# MercurialSDR_FTDI.net
KiCad netlist of a schematic drawn in Altium Designer
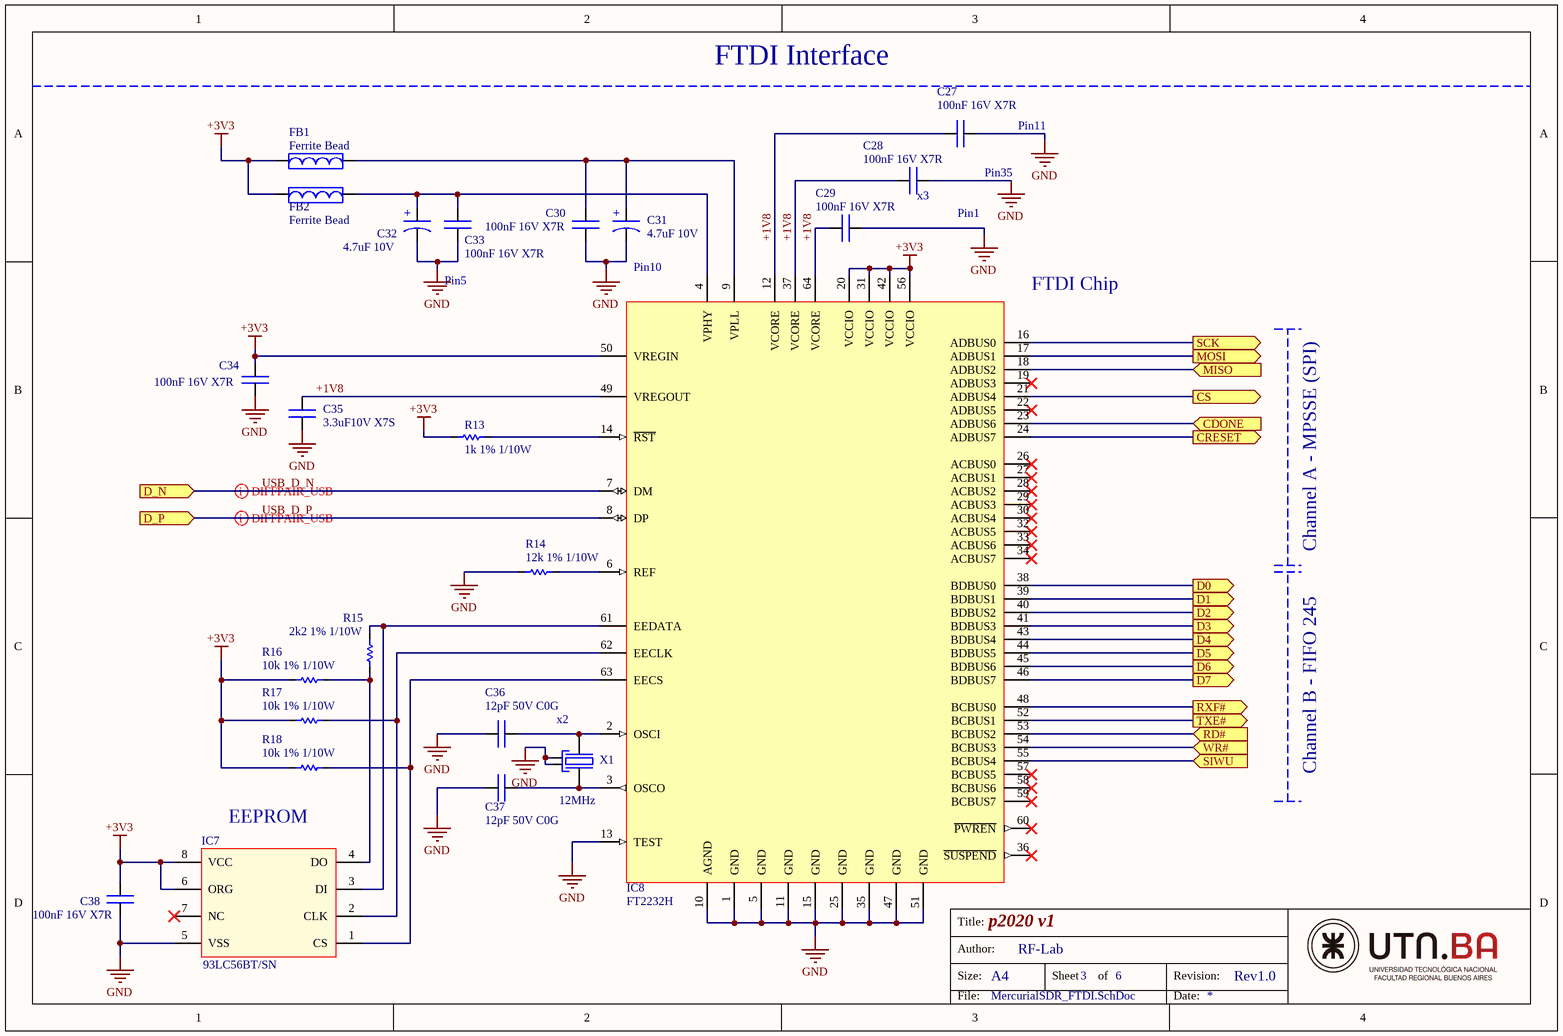
[diagram p0: MercurialSDR_FTDI.SchDoc]

(export (version "E")
  (design (tool "Eeschema 10.0.6"))
  (components
    (comp (ref "C27")
      (value "100nF 16V X7R")
      (footprint "CAP_0603")
      (description "Capacitor no polarizado")
      (fields (field (name "Comment") "100nF 16V X7R - CL10B104KO8NNNC"))
      (libsource (lib "MercurialSDR") (part "Cap"))
    )
    (comp (ref "C28")
      (value "100nF 16V X7R")
      (footprint "CAP_0603")
      (description "Capacitor no polarizado")
      (fields (field (name "Comment") "100nF 16V X7R - CL10B104KO8NNNC"))
      (libsource (lib "MercurialSDR") (part "Cap"))
    )
    (comp (ref "C29")
      (value "100nF 16V X7R")
      (footprint "CAP_0603")
      (description "Capacitor no polarizado")
      (fields (field (name "Comment") "100nF 16V X7R - CL10B104KO8NNNC"))
      (libsource (lib "MercurialSDR") (part "Cap"))
    )
    (comp (ref "C30")
      (value "100nF 16V X7R")
      (footprint "CAP_0603")
      (description "Capacitor no polarizado")
      (fields (field (name "Comment") "100nF 16V X7R - CL10B104KO8NNNC"))
      (libsource (lib "MercurialSDR") (part "Cap"))
    )
    (comp (ref "C31")
      (value "4.7uF 10V")
      (footprint "CAP_TANT_1206")
      (description "Capacitor polarizado")
      (fields (field (name "Comment") "4.7uF 10V - TAJA475K010RNJ"))
      (libsource (lib "MercurialSDR") (part "Cap Pol"))
    )
    (comp (ref "C32")
      (value "4.7uF 10V")
      (footprint "CAP_TANT_1206")
      (description "Capacitor polarizado")
      (fields (field (name "Comment") "4.7uF 10V - TAJA475K010RNJ"))
      (libsource (lib "MercurialSDR") (part "Cap Pol"))
    )
    (comp (ref "C33")
      (value "100nF 16V X7R")
      (footprint "CAP_0603")
      (description "Capacitor no polarizado")
      (fields (field (name "Comment") "100nF 16V X7R - CL10B104KO8NNNC"))
      (libsource (lib "MercurialSDR") (part "Cap"))
    )
    (comp (ref "C34")
      (value "100nF 16V X7R")
      (footprint "CAP_0603")
      (description "Capacitor no polarizado")
      (fields (field (name "Comment") "100nF 16V X7R - CL10B104KO8NNNC"))
      (libsource (lib "MercurialSDR") (part "Cap"))
    )
    (comp (ref "C35")
      (value "3.3uF10V X7S")
      (footprint "CAP_0603")
      (description "Capacitor no polarizado")
      (fields (field (name "Comment") "3.3uF10V X7S - C1608X7S1A335K080AC"))
      (libsource (lib "MercurialSDR") (part "Cap"))
    )
    (comp (ref "C36")
      (value "12pF 50V C0G")
      (footprint "CAP_0603")
      (description "Capacitor no polarizado")
      (fields (field (name "Comment") "12pF 50V C0G - CL10C120JB8NNNC"))
      (libsource (lib "MercurialSDR") (part "Cap"))
    )
    (comp (ref "C37")
      (value "12pF 50V C0G")
      (footprint "CAP_0603")
      (description "Capacitor no polarizado")
      (fields (field (name "Comment") "12pF 50V C0G - CL10C120JB8NNNC"))
      (libsource (lib "MercurialSDR") (part "Cap"))
    )
    (comp (ref "C38")
      (value "100nF 16V X7R")
      (footprint "CAP_0603")
      (description "Capacitor no polarizado")
      (fields
        (field (name "PART NUMBER") "CL10B104KO8NNNC")
        (field (name "Comment") "100nF 16V X7R - CL10B104KO8NNNC")
      )
      (libsource (lib "MercurialSDR") (part "Cap"))
    )
    (comp (ref "FB1")
      (value "BLM18AG121SN1D")
      (footprint "FERRITE_BEAD_0603")
      (description "Ferrite Bead")
      (fields (field (name "IN") "Ferrite Bead"))
      (libsource (lib "MercurialSDR") (part "Ferrite Bead"))
    )
    (comp (ref "FB2")
      (value "BLM18AG121SN1D")
      (footprint "FERRITE_BEAD_0603")
      (description "Ferrite Bead")
      (fields (field (name "IN") "Ferrite Bead"))
      (libsource (lib "MercurialSDR") (part "Ferrite Bead"))
    )
    (comp (ref "IC7")
      (value "93LC56BT")
      (footprint "SOIC-8")
      (description "EEPROM SPI 2kb (128x16)")
      (fields (field (name "PART NUMBER") "93LC56BT/SN"))
      (libsource (lib "MercurialSDR") (part "93LC56BT/SN"))
    )
    (comp (ref "IC8")
      (value "FT2232H")
      (footprint "LQFP_64")
      (description "USB bridge")
      (fields (field (name "Comment") "FT2232HL-TRAY"))
      (libsource (lib "MercurialSDR") (part "FT2232H"))
    )
    (comp (ref "R13")
      (value "1k 1% 1/10W")
      (footprint "RES_0603")
      (description "Resistor")
      (fields (field (name "Comment") "1k 1% 1/10W - CR0603-FX-1001ELF"))
      (libsource (lib "MercurialSDR") (part "Res"))
    )
    (comp (ref "R14")
      (value "12k 1% 1/10W")
      (footprint "RES_0603")
      (description "Resistor")
      (fields (field (name "POWER") "1/10W") (field (name "PART NUMBER") "CR0603-FX-1202ELF"))
      (libsource (lib "MercurialSDR") (part "Res"))
    )
    (comp (ref "R15")
      (value "2k2 1% 1/10W")
      (footprint "RES_0603")
      (description "Resistor")
      (fields (field (name "Comment") "2k2 1% 1/10W - AC0603FR-072K2L"))
      (libsource (lib "MercurialSDR") (part "Res"))
    )
    (comp (ref "R16")
      (value "10k 1% 1/10W")
      (footprint "RES_0603")
      (description "Resistor")
      (fields (field (name "Comment") "10k 1% 1/10W - CR0603-FX-1002EAS"))
      (libsource (lib "MercurialSDR") (part "Res"))
    )
    (comp (ref "R17")
      (value "10k 1% 1/10W")
      (footprint "RES_0603")
      (description "Resistor")
      (fields (field (name "Comment") "10k 1% 1/10W - CR0603-FX-1002EAS"))
      (libsource (lib "MercurialSDR") (part "Res"))
    )
    (comp (ref "R18")
      (value "10k 1% 1/10W")
      (footprint "RES_0603")
      (description "Resistor")
      (fields (field (name "Comment") "10k 1% 1/10W - CR0603-FX-1002EAS"))
      (libsource (lib "MercurialSDR") (part "Res"))
    )
    (comp (ref "X1")
      (value "12MHz")
      (footprint "XTAL_3.2x2.5")
      (description "Oscilador a Cristal")
      (fields (field (name "PART NUMBER") "ECS-120-12-33-AGN-TR"))
      (libsource (lib "MercurialSDR") (part "XTAL_4term"))
    )
  )
  (nets
    (net (code "1") (name "+3V3") (class "Default")
      (node (ref "C34") (pin "1") (pinfunction "1_1") (pintype "passive"))
      (node (ref "C38") (pin "1") (pinfunction "1_1") (pintype "passive"))
      (node (ref "FB1") (pin "1") (pinfunction "1_1") (pintype "passive"))
      (node (ref "FB2") (pin "1") (pinfunction "1_1") (pintype "passive"))
      (node (ref "IC7") (pin "6") (pinfunction "ORG_6") (pintype "passive"))
      (node (ref "IC7") (pin "8") (pinfunction "VCC_8") (pintype "passive"))
      (node (ref "IC8") (pin "20") (pinfunction "VCCIO_20") (pintype "power_in"))
      (node (ref "IC8") (pin "31") (pinfunction "VCCIO_31") (pintype "power_in"))
      (node (ref "IC8") (pin "42") (pinfunction "VCCIO_42") (pintype "power_in"))
      (node (ref "IC8") (pin "50") (pinfunction "VREGIN_50") (pintype "power_in"))
      (node (ref "IC8") (pin "56") (pinfunction "VCCIO_56") (pintype "power_in"))
      (node (ref "R13") (pin "2") (pinfunction "2_2") (pintype "passive"))
      (node (ref "R16") (pin "2") (pinfunction "2_2") (pintype "passive"))
      (node (ref "R17") (pin "1") (pinfunction "1_1") (pintype "passive"))
      (node (ref "R18") (pin "1") (pinfunction "1_1") (pintype "passive"))
    )
    (net (code "2") (name "/+1V8") (class "Default")
      (node (ref "C27") (pin "1") (pinfunction "1_1") (pintype "passive"))
      (node (ref "C28") (pin "1") (pinfunction "1_1") (pintype "passive"))
      (node (ref "C29") (pin "1") (pinfunction "1_1") (pintype "passive"))
      (node (ref "C35") (pin "1") (pinfunction "1_1") (pintype "passive"))
      (node (ref "IC8") (pin "12") (pinfunction "VCORE_12") (pintype "power_in"))
      (node (ref "IC8") (pin "37") (pinfunction "VCORE_37") (pintype "power_in"))
      (node (ref "IC8") (pin "49") (pinfunction "VREGOUT_49") (pintype "power_in"))
      (node (ref "IC8") (pin "64") (pinfunction "VCORE_64") (pintype "power_in"))
    )
    (net (code "3") (name "/CDONE") (class "Default")
      (node (ref "IC8") (pin "23") (pinfunction "ADBUS6_23") (pintype "passive"))
    )
    (net (code "4") (name "/CRESET") (class "Default")
      (node (ref "IC8") (pin "24") (pinfunction "ADBUS7_24") (pintype "passive"))
    )
    (net (code "5") (name "/CS") (class "Default")
      (node (ref "IC8") (pin "21") (pinfunction "ADBUS4_21") (pintype "passive"))
    )
    (net (code "6") (name "/D0") (class "Default")
      (node (ref "IC8") (pin "38") (pinfunction "BDBUS0_38") (pintype "passive"))
    )
    (net (code "7") (name "/D1") (class "Default")
      (node (ref "IC8") (pin "39") (pinfunction "BDBUS1_39") (pintype "passive"))
    )
    (net (code "8") (name "/D2") (class "Default")
      (node (ref "IC8") (pin "40") (pinfunction "BDBUS2_40") (pintype "passive"))
    )
    (net (code "9") (name "/D3") (class "Default")
      (node (ref "IC8") (pin "41") (pinfunction "BDBUS3_41") (pintype "passive"))
    )
    (net (code "10") (name "/D4") (class "Default")
      (node (ref "IC8") (pin "43") (pinfunction "BDBUS4_43") (pintype "passive"))
    )
    (net (code "11") (name "/D5") (class "Default")
      (node (ref "IC8") (pin "44") (pinfunction "BDBUS5_44") (pintype "passive"))
    )
    (net (code "12") (name "/D6") (class "Default")
      (node (ref "IC8") (pin "45") (pinfunction "BDBUS6_45") (pintype "passive"))
    )
    (net (code "13") (name "/D7") (class "Default")
      (node (ref "IC8") (pin "46") (pinfunction "BDBUS7_46") (pintype "passive"))
    )
    (net (code "14") (name "/MISO") (class "Default")
      (node (ref "IC8") (pin "18") (pinfunction "ADBUS2_18") (pintype "passive"))
    )
    (net (code "15") (name "/MOSI") (class "Default")
      (node (ref "IC8") (pin "17") (pinfunction "ADBUS1_17") (pintype "passive"))
    )
    (net (code "16") (name "/RD#") (class "Default")
      (node (ref "IC8") (pin "53") (pinfunction "BCBUS2_53") (pintype "passive"))
    )
    (net (code "17") (name "/RXF#") (class "Default")
      (node (ref "IC8") (pin "48") (pinfunction "BCBUS0_48") (pintype "passive"))
    )
    (net (code "18") (name "/SCK") (class "Default")
      (node (ref "IC8") (pin "16") (pinfunction "ADBUS0_16") (pintype "passive"))
    )
    (net (code "19") (name "/SIWU") (class "Default")
      (node (ref "IC8") (pin "55") (pinfunction "BCBUS4_55") (pintype "passive"))
    )
    (net (code "20") (name "/TXE#") (class "Default")
      (node (ref "IC8") (pin "52") (pinfunction "BCBUS1_52") (pintype "passive"))
    )
    (net (code "21") (name "/USB_D_N") (class "Default")
      (node (ref "IC8") (pin "7") (pinfunction "DM_7") (pintype "bidirectional"))
    )
    (net (code "22") (name "/USB_D_P") (class "Default")
      (node (ref "IC8") (pin "8") (pinfunction "DP_8") (pintype "bidirectional"))
    )
    (net (code "23") (name "/WR#") (class "Default")
      (node (ref "IC8") (pin "54") (pinfunction "BCBUS3_54") (pintype "passive"))
    )
    (net (code "24") (name "GND") (class "Default")
      (node (ref "C27") (pin "2") (pinfunction "2_2") (pintype "passive"))
      (node (ref "C28") (pin "2") (pinfunction "2_2") (pintype "passive"))
      (node (ref "C29") (pin "2") (pinfunction "2_2") (pintype "passive"))
      (node (ref "C30") (pin "2") (pinfunction "2_2") (pintype "passive"))
      (node (ref "C31") (pin "2") (pinfunction "2_2") (pintype "passive"))
      (node (ref "C32") (pin "2") (pinfunction "2_2") (pintype "passive"))
      (node (ref "C33") (pin "2") (pinfunction "2_2") (pintype "passive"))
      (node (ref "C34") (pin "2") (pinfunction "2_2") (pintype "passive"))
      (node (ref "C35") (pin "2") (pinfunction "2_2") (pintype "passive"))
      (node (ref "C36") (pin "2") (pinfunction "2_2") (pintype "passive"))
      (node (ref "C37") (pin "1") (pinfunction "1_1") (pintype "passive"))
      (node (ref "C38") (pin "2") (pinfunction "2_2") (pintype "passive"))
      (node (ref "IC7") (pin "5") (pinfunction "VSS_5") (pintype "passive"))
      (node (ref "IC8") (pin "1") (pinfunction "GND_1") (pintype "power_in"))
      (node (ref "IC8") (pin "10") (pinfunction "AGND_10") (pintype "power_in"))
      (node (ref "IC8") (pin "11") (pinfunction "GND_11") (pintype "power_in"))
      (node (ref "IC8") (pin "13") (pinfunction "TEST_13") (pintype "input"))
      (node (ref "IC8") (pin "15") (pinfunction "GND_15") (pintype "power_in"))
      (node (ref "IC8") (pin "25") (pinfunction "GND_25") (pintype "power_in"))
      (node (ref "IC8") (pin "35") (pinfunction "GND_35") (pintype "power_in"))
      (node (ref "IC8") (pin "47") (pinfunction "GND_47") (pintype "power_in"))
      (node (ref "IC8") (pin "5") (pinfunction "GND_5") (pintype "power_in"))
      (node (ref "IC8") (pin "51") (pinfunction "GND_51") (pintype "power_in"))
      (node (ref "R14") (pin "2") (pinfunction "2_2") (pintype "passive"))
      (node (ref "X1") (pin "2") (pinfunction "2_2") (pintype "passive"))
      (node (ref "X1") (pin "4") (pinfunction "4_4") (pintype "passive"))
    )
    (net (code "25") (name "Net-(IC7-CLK)") (class "Default")
      (node (ref "IC7") (pin "2") (pinfunction "CLK_2") (pintype "passive"))
      (node (ref "IC8") (pin "62") (pinfunction "EECLK_62") (pintype "passive"))
      (node (ref "R17") (pin "2") (pinfunction "2_2") (pintype "passive"))
    )
    (net (code "26") (name "Net-(IC7-CS)") (class "Default")
      (node (ref "IC7") (pin "1") (pinfunction "CS_1") (pintype "passive"))
      (node (ref "IC8") (pin "63") (pinfunction "EECS_63") (pintype "passive"))
      (node (ref "R18") (pin "2") (pinfunction "2_2") (pintype "passive"))
    )
    (net (code "27") (name "Net-(IC7-DI)") (class "Default")
      (node (ref "IC7") (pin "3") (pinfunction "DI_3") (pintype "passive"))
      (node (ref "IC8") (pin "61") (pinfunction "EEDATA_61") (pintype "passive"))
      (node (ref "R15") (pin "2") (pinfunction "2_2") (pintype "passive"))
    )
    (net (code "28") (name "Net-(IC7-DO)") (class "Default")
      (node (ref "IC7") (pin "4") (pinfunction "DO_4") (pintype "passive"))
      (node (ref "R15") (pin "1") (pinfunction "1_1") (pintype "passive"))
      (node (ref "R16") (pin "1") (pinfunction "1_1") (pintype "passive"))
    )
    (net (code "29") (name "Net-(IC8-OSCI)") (class "Default")
      (node (ref "C36") (pin "1") (pinfunction "1_1") (pintype "passive"))
      (node (ref "IC8") (pin "2") (pinfunction "OSCI_2") (pintype "input"))
      (node (ref "X1") (pin "1") (pinfunction "1_1") (pintype "passive"))
    )
    (net (code "30") (name "Net-(IC8-OSCO)") (class "Default")
      (node (ref "C37") (pin "2") (pinfunction "2_2") (pintype "passive"))
      (node (ref "IC8") (pin "3") (pinfunction "OSCO_3") (pintype "output"))
      (node (ref "X1") (pin "3") (pinfunction "3_3") (pintype "passive"))
    )
    (net (code "31") (name "Net-(IC8-REF)") (class "Default")
      (node (ref "IC8") (pin "6") (pinfunction "REF_6") (pintype "input"))
      (node (ref "R14") (pin "1") (pinfunction "1_1") (pintype "passive"))
    )
    (net (code "32") (name "Net-(IC8-VPHY)") (class "Default")
      (node (ref "C32") (pin "1") (pinfunction "1_1") (pintype "passive"))
      (node (ref "C33") (pin "1") (pinfunction "1_1") (pintype "passive"))
      (node (ref "FB2") (pin "2") (pinfunction "2_2") (pintype "passive"))
      (node (ref "IC8") (pin "4") (pinfunction "VPHY_4") (pintype "power_in"))
    )
    (net (code "33") (name "Net-(IC8-VPLL)") (class "Default")
      (node (ref "C30") (pin "1") (pinfunction "1_1") (pintype "passive"))
      (node (ref "C31") (pin "1") (pinfunction "1_1") (pintype "passive"))
      (node (ref "FB1") (pin "2") (pinfunction "2_2") (pintype "passive"))
      (node (ref "IC8") (pin "9") (pinfunction "VPLL_9") (pintype "power_in"))
    )
    (net (code "34") (name "Net-(IC8-~{RST})") (class "Default")
      (node (ref "IC8") (pin "14") (pinfunction "~{RST}_14") (pintype "input"))
      (node (ref "R13") (pin "1") (pinfunction "1_1") (pintype "passive"))
    )
    (net (code "35") (name "unconnected-(IC7-NC-Pad7)") (class "Default")
      (node (ref "IC7") (pin "7") (pinfunction "NC_7") (pintype "passive+no_connect"))
    )
    (net (code "36") (name "unconnected-(IC8-ACBUS0-Pad26)") (class "Default")
      (node (ref "IC8") (pin "26") (pinfunction "ACBUS0_26") (pintype "passive+no_connect"))
    )
    (net (code "37") (name "unconnected-(IC8-ACBUS1-Pad27)") (class "Default")
      (node (ref "IC8") (pin "27") (pinfunction "ACBUS1_27") (pintype "passive+no_connect"))
    )
    (net (code "38") (name "unconnected-(IC8-ACBUS2-Pad28)") (class "Default")
      (node (ref "IC8") (pin "28") (pinfunction "ACBUS2_28") (pintype "passive+no_connect"))
    )
    (net (code "39") (name "unconnected-(IC8-ACBUS3-Pad29)") (class "Default")
      (node (ref "IC8") (pin "29") (pinfunction "ACBUS3_29") (pintype "passive+no_connect"))
    )
    (net (code "40") (name "unconnected-(IC8-ACBUS4-Pad30)") (class "Default")
      (node (ref "IC8") (pin "30") (pinfunction "ACBUS4_30") (pintype "passive+no_connect"))
    )
    (net (code "41") (name "unconnected-(IC8-ACBUS5-Pad32)") (class "Default")
      (node (ref "IC8") (pin "32") (pinfunction "ACBUS5_32") (pintype "passive+no_connect"))
    )
    (net (code "42") (name "unconnected-(IC8-ACBUS6-Pad33)") (class "Default")
      (node (ref "IC8") (pin "33") (pinfunction "ACBUS6_33") (pintype "passive+no_connect"))
    )
    (net (code "43") (name "unconnected-(IC8-ACBUS7-Pad34)") (class "Default")
      (node (ref "IC8") (pin "34") (pinfunction "ACBUS7_34") (pintype "passive+no_connect"))
    )
    (net (code "44") (name "unconnected-(IC8-ADBUS3-Pad19)") (class "Default")
      (node (ref "IC8") (pin "19") (pinfunction "ADBUS3_19") (pintype "passive+no_connect"))
    )
    (net (code "45") (name "unconnected-(IC8-ADBUS5-Pad22)") (class "Default")
      (node (ref "IC8") (pin "22") (pinfunction "ADBUS5_22") (pintype "passive+no_connect"))
    )
    (net (code "46") (name "unconnected-(IC8-BCBUS5-Pad57)") (class "Default")
      (node (ref "IC8") (pin "57") (pinfunction "BCBUS5_57") (pintype "passive+no_connect"))
    )
    (net (code "47") (name "unconnected-(IC8-BCBUS6-Pad58)") (class "Default")
      (node (ref "IC8") (pin "58") (pinfunction "BCBUS6_58") (pintype "passive+no_connect"))
    )
    (net (code "48") (name "unconnected-(IC8-BCBUS7-Pad59)") (class "Default")
      (node (ref "IC8") (pin "59") (pinfunction "BCBUS7_59") (pintype "passive+no_connect"))
    )
    (net (code "49") (name "unconnected-(IC8-~{PWREN}-Pad60)") (class "Default")
      (node (ref "IC8") (pin "60") (pinfunction "~{PWREN}_60") (pintype "output+no_connect"))
    )
    (net (code "50") (name "unconnected-(IC8-~{SUSPEND}-Pad36)") (class "Default")
      (node (ref "IC8") (pin "36") (pinfunction "~{SUSPEND}_36") (pintype "output+no_connect"))
    )
  )
)
